# ultrasonic-breakout-pth.net
KiCad netlist of a schematic drawn in EAGLE
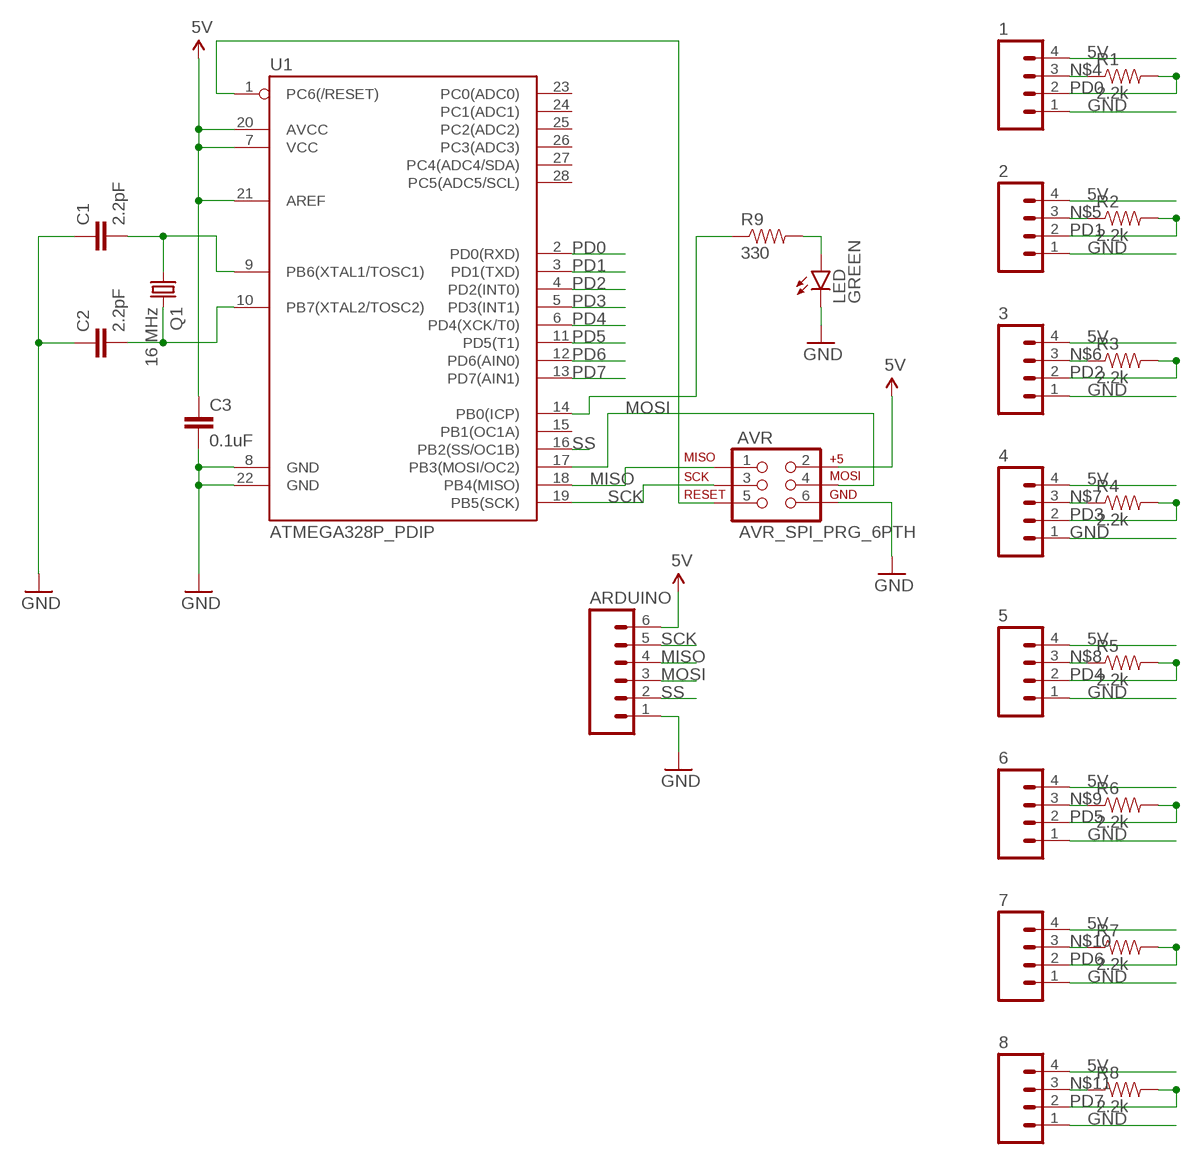
[diagram p0: schematic, sheet 1]

(export (version "E")
  (design (tool "Eeschema 10.0.6"))
  (components
    (comp (ref "1")
      (value "M04LOCK")
      (footprint "eagle-import:1X04_LOCK")
      (libsource (lib "eagle-import") (part "M04LOCK"))
    )
    (comp (ref "2")
      (value "M04LOCK")
      (footprint "eagle-import:1X04_LOCK")
      (libsource (lib "eagle-import") (part "M04LOCK"))
    )
    (comp (ref "3")
      (value "M04LOCK")
      (footprint "eagle-import:1X04_LOCK")
      (libsource (lib "eagle-import") (part "M04LOCK"))
    )
    (comp (ref "4")
      (value "M04LOCK")
      (footprint "eagle-import:1X04_LOCK")
      (libsource (lib "eagle-import") (part "M04LOCK"))
    )
    (comp (ref "5")
      (value "M04LOCK")
      (footprint "eagle-import:1X04_LOCK")
      (libsource (lib "eagle-import") (part "M04LOCK"))
    )
    (comp (ref "6")
      (value "M04LOCK")
      (footprint "eagle-import:1X04_LOCK")
      (libsource (lib "eagle-import") (part "M04LOCK"))
    )
    (comp (ref "7")
      (value "M04LOCK")
      (footprint "eagle-import:1X04_LOCK")
      (libsource (lib "eagle-import") (part "M04LOCK"))
    )
    (comp (ref "8")
      (value "M04LOCK")
      (footprint "eagle-import:1X04_LOCK")
      (libsource (lib "eagle-import") (part "M04LOCK"))
    )
    (comp (ref "ARDUINO")
      (value "M06LOCK")
      (footprint "eagle-import:1X06_LOCK")
      (libsource (lib "eagle-import") (part "M06LOCK"))
    )
    (comp (ref "AVR")
      (value "AVR_SPI_PRG_6PTH")
      (footprint "eagle-import:2X3")
      (libsource (lib "eagle-import") (part "AVR_SPI_PRG_6PTH"))
    )
    (comp (ref "C1")
      (value "2.2pF")
      (footprint "eagle-import:CAP-PTH-SMALL")
      (libsource (lib "eagle-import") (part "SparkFun-Passives_CAPPTH"))
    )
    (comp (ref "C2")
      (value "2.2pF")
      (footprint "eagle-import:CAP-PTH-SMALL")
      (libsource (lib "eagle-import") (part "SparkFun-Passives_CAPPTH"))
    )
    (comp (ref "C3")
      (value "0.1uF")
      (footprint "eagle-import:CAP-PTH-5MM")
      (libsource (lib "eagle-import") (part "CAPPTH1"))
    )
    (comp (ref "LED")
      (value "GREEN")
      (footprint "eagle-import:LED5MM")
      (libsource (lib "eagle-import") (part "LED5MM"))
    )
    (comp (ref "Q1")
      (value "16 MHz")
      (footprint "eagle-import:HC49U-V")
      (libsource (lib "eagle-import") (part "CRYSTALHC49UV"))
    )
    (comp (ref "R1")
      (value "2.2k")
      (footprint "eagle-import:AXIAL-0.4")
      (libsource (lib "eagle-import") (part "RESISTORPTH-1/4W"))
    )
    (comp (ref "R2")
      (value "2.2k")
      (footprint "eagle-import:AXIAL-0.4")
      (libsource (lib "eagle-import") (part "RESISTORPTH-1/4W"))
    )
    (comp (ref "R3")
      (value "2.2k")
      (footprint "eagle-import:AXIAL-0.4")
      (libsource (lib "eagle-import") (part "RESISTORPTH-1/4W"))
    )
    (comp (ref "R4")
      (value "2.2k")
      (footprint "eagle-import:AXIAL-0.4")
      (libsource (lib "eagle-import") (part "RESISTORPTH-1/4W"))
    )
    (comp (ref "R5")
      (value "2.2k")
      (footprint "eagle-import:AXIAL-0.4")
      (libsource (lib "eagle-import") (part "RESISTORPTH-1/4W"))
    )
    (comp (ref "R6")
      (value "2.2k")
      (footprint "eagle-import:AXIAL-0.4")
      (libsource (lib "eagle-import") (part "RESISTORPTH-1/4W"))
    )
    (comp (ref "R7")
      (value "2.2k")
      (footprint "eagle-import:AXIAL-0.4")
      (libsource (lib "eagle-import") (part "RESISTORPTH-1/4W"))
    )
    (comp (ref "R8")
      (value "2.2k")
      (footprint "eagle-import:AXIAL-0.4")
      (libsource (lib "eagle-import") (part "RESISTORPTH-1/4W"))
    )
    (comp (ref "R9")
      (value "330")
      (footprint "eagle-import:AXIAL-0.4")
      (libsource (lib "eagle-import") (part "RESISTORPTH-1/4W"))
    )
    (comp (ref "U1")
      (value "ATMEGA328P_PDIP")
      (footprint "eagle-import:DIL28-3")
      (libsource (lib "eagle-import") (part "ATMEGA328P_PDIP"))
    )
  )
  (nets
    (net (code "1") (name "/MISO") (class "Default")
      (node (ref "ARDUINO") (pin "4") (pinfunction "4_4") (pintype "passive"))
      (node (ref "AVR") (pin "1") (pinfunction "1_1") (pintype "passive"))
      (node (ref "U1") (pin "18") (pinfunction "PB4(MISO)_18") (pintype "bidirectional"))
    )
    (net (code "2") (name "/MOSI") (class "Default")
      (node (ref "ARDUINO") (pin "3") (pinfunction "3_3") (pintype "passive"))
      (node (ref "AVR") (pin "4") (pinfunction "4_4") (pintype "passive"))
      (node (ref "U1") (pin "17") (pinfunction "PB3(MOSI/OC2)_17") (pintype "bidirectional"))
    )
    (net (code "3") (name "/N$4") (class "Default")
      (node (ref "1") (pin "3") (pinfunction "3_3") (pintype "passive"))
      (node (ref "R1") (pin "P$1") (pinfunction "1_P$1") (pintype "passive"))
    )
    (net (code "4") (name "/N$5") (class "Default")
      (node (ref "2") (pin "3") (pinfunction "3_3") (pintype "passive"))
      (node (ref "R2") (pin "P$1") (pinfunction "1_P$1") (pintype "passive"))
    )
    (net (code "5") (name "/N$6") (class "Default")
      (node (ref "3") (pin "3") (pinfunction "3_3") (pintype "passive"))
      (node (ref "R3") (pin "P$1") (pinfunction "1_P$1") (pintype "passive"))
    )
    (net (code "6") (name "/N$7") (class "Default")
      (node (ref "4") (pin "3") (pinfunction "3_3") (pintype "passive"))
      (node (ref "R4") (pin "P$1") (pinfunction "1_P$1") (pintype "passive"))
    )
    (net (code "7") (name "/N$8") (class "Default")
      (node (ref "5") (pin "3") (pinfunction "3_3") (pintype "passive"))
      (node (ref "R5") (pin "P$1") (pinfunction "1_P$1") (pintype "passive"))
    )
    (net (code "8") (name "/N$9") (class "Default")
      (node (ref "6") (pin "3") (pinfunction "3_3") (pintype "passive"))
      (node (ref "R6") (pin "P$1") (pinfunction "1_P$1") (pintype "passive"))
    )
    (net (code "9") (name "/N$10") (class "Default")
      (node (ref "7") (pin "3") (pinfunction "3_3") (pintype "passive"))
      (node (ref "R7") (pin "P$1") (pinfunction "1_P$1") (pintype "passive"))
    )
    (net (code "10") (name "/N$11") (class "Default")
      (node (ref "8") (pin "3") (pinfunction "3_3") (pintype "passive"))
      (node (ref "R8") (pin "P$1") (pinfunction "1_P$1") (pintype "passive"))
    )
    (net (code "11") (name "/PD0") (class "Default")
      (node (ref "1") (pin "2") (pinfunction "2_2") (pintype "passive"))
      (node (ref "R1") (pin "P$2") (pinfunction "2_P$2") (pintype "passive"))
      (node (ref "U1") (pin "2") (pinfunction "PD0(RXD)_2") (pintype "bidirectional"))
    )
    (net (code "12") (name "/PD1") (class "Default")
      (node (ref "2") (pin "2") (pinfunction "2_2") (pintype "passive"))
      (node (ref "R2") (pin "P$2") (pinfunction "2_P$2") (pintype "passive"))
      (node (ref "U1") (pin "3") (pinfunction "PD1(TXD)_3") (pintype "bidirectional"))
    )
    (net (code "13") (name "/PD2") (class "Default")
      (node (ref "3") (pin "2") (pinfunction "2_2") (pintype "passive"))
      (node (ref "R3") (pin "P$2") (pinfunction "2_P$2") (pintype "passive"))
      (node (ref "U1") (pin "4") (pinfunction "PD2(INT0)_4") (pintype "bidirectional"))
    )
    (net (code "14") (name "/PD3") (class "Default")
      (node (ref "4") (pin "2") (pinfunction "2_2") (pintype "passive"))
      (node (ref "R4") (pin "P$2") (pinfunction "2_P$2") (pintype "passive"))
      (node (ref "U1") (pin "5") (pinfunction "PD3(INT1)_5") (pintype "bidirectional"))
    )
    (net (code "15") (name "/PD4") (class "Default")
      (node (ref "5") (pin "2") (pinfunction "2_2") (pintype "passive"))
      (node (ref "R5") (pin "P$2") (pinfunction "2_P$2") (pintype "passive"))
      (node (ref "U1") (pin "6") (pinfunction "PD4(XCK/T0)_6") (pintype "bidirectional"))
    )
    (net (code "16") (name "/PD5") (class "Default")
      (node (ref "6") (pin "2") (pinfunction "2_2") (pintype "passive"))
      (node (ref "R6") (pin "P$2") (pinfunction "2_P$2") (pintype "passive"))
      (node (ref "U1") (pin "11") (pinfunction "PD5(T1)_11") (pintype "bidirectional"))
    )
    (net (code "17") (name "/PD6") (class "Default")
      (node (ref "7") (pin "2") (pinfunction "2_2") (pintype "passive"))
      (node (ref "R7") (pin "P$2") (pinfunction "2_P$2") (pintype "passive"))
      (node (ref "U1") (pin "12") (pinfunction "PD6(AIN0)_12") (pintype "bidirectional"))
    )
    (net (code "18") (name "/PD7") (class "Default")
      (node (ref "8") (pin "2") (pinfunction "2_2") (pintype "passive"))
      (node (ref "R8") (pin "P$2") (pinfunction "2_P$2") (pintype "passive"))
      (node (ref "U1") (pin "13") (pinfunction "PD7(AIN1)_13") (pintype "bidirectional"))
    )
    (net (code "19") (name "/SCK") (class "Default")
      (node (ref "ARDUINO") (pin "5") (pinfunction "5_5") (pintype "passive"))
      (node (ref "AVR") (pin "3") (pinfunction "3_3") (pintype "passive"))
      (node (ref "U1") (pin "19") (pinfunction "PB5(SCK)_19") (pintype "bidirectional"))
    )
    (net (code "20") (name "/SS") (class "Default")
      (node (ref "ARDUINO") (pin "2") (pinfunction "2_2") (pintype "passive"))
      (node (ref "U1") (pin "16") (pinfunction "PB2(SS/OC1B)_16") (pintype "bidirectional"))
    )
    (net (code "21") (name "5V") (class "Default")
      (node (ref "1") (pin "4") (pinfunction "4_4") (pintype "passive"))
      (node (ref "2") (pin "4") (pinfunction "4_4") (pintype "passive"))
      (node (ref "3") (pin "4") (pinfunction "4_4") (pintype "passive"))
      (node (ref "4") (pin "4") (pinfunction "4_4") (pintype "passive"))
      (node (ref "5") (pin "4") (pinfunction "4_4") (pintype "passive"))
      (node (ref "6") (pin "4") (pinfunction "4_4") (pintype "passive"))
      (node (ref "7") (pin "4") (pinfunction "4_4") (pintype "passive"))
      (node (ref "8") (pin "4") (pinfunction "4_4") (pintype "passive"))
      (node (ref "ARDUINO") (pin "6") (pinfunction "6_6") (pintype "passive"))
      (node (ref "AVR") (pin "2") (pinfunction "2_2") (pintype "passive"))
      (node (ref "C3") (pin "1") (pinfunction "1_1") (pintype "passive"))
      (node (ref "U1") (pin "20") (pinfunction "AVCC_20") (pintype "bidirectional"))
      (node (ref "U1") (pin "21") (pinfunction "AREF_21") (pintype "bidirectional"))
      (node (ref "U1") (pin "7") (pinfunction "VCC_7") (pintype "bidirectional"))
    )
    (net (code "22") (name "GND") (class "Default")
      (node (ref "1") (pin "1") (pinfunction "1_1") (pintype "passive"))
      (node (ref "2") (pin "1") (pinfunction "1_1") (pintype "passive"))
      (node (ref "3") (pin "1") (pinfunction "1_1") (pintype "passive"))
      (node (ref "4") (pin "1") (pinfunction "1_1") (pintype "passive"))
      (node (ref "5") (pin "1") (pinfunction "1_1") (pintype "passive"))
      (node (ref "6") (pin "1") (pinfunction "1_1") (pintype "passive"))
      (node (ref "7") (pin "1") (pinfunction "1_1") (pintype "passive"))
      (node (ref "8") (pin "1") (pinfunction "1_1") (pintype "passive"))
      (node (ref "ARDUINO") (pin "1") (pinfunction "1_1") (pintype "passive"))
      (node (ref "AVR") (pin "6") (pinfunction "6_6") (pintype "passive"))
      (node (ref "C1") (pin "1") (pinfunction "1_1") (pintype "passive"))
      (node (ref "C2") (pin "1") (pinfunction "1_1") (pintype "passive"))
      (node (ref "C3") (pin "2") (pinfunction "2_2") (pintype "passive"))
      (node (ref "LED") (pin "K") (pinfunction "C_K") (pintype "passive"))
      (node (ref "U1") (pin "22") (pinfunction "GND_22") (pintype "bidirectional"))
      (node (ref "U1") (pin "8") (pinfunction "GND_8") (pintype "bidirectional"))
    )
    (net (code "23") (name "Net-(R9-1)") (class "Default")
      (node (ref "R9") (pin "P$1") (pinfunction "1_P$1") (pintype "passive"))
      (node (ref "U1") (pin "14") (pinfunction "PB0(ICP)_14") (pintype "bidirectional"))
    )
    (net (code "24") (name "Net-(R9-2)") (class "Default")
      (node (ref "LED") (pin "A") (pinfunction "A_A") (pintype "passive"))
      (node (ref "R9") (pin "P$2") (pinfunction "2_P$2") (pintype "passive"))
    )
    (net (code "25") (name "Net-(U1-PB6(XTAL1{slash}TOSC1))") (class "Default")
      (node (ref "C1") (pin "2") (pinfunction "2_2") (pintype "passive"))
      (node (ref "Q1") (pin "1") (pinfunction "1_1") (pintype "passive"))
      (node (ref "U1") (pin "9") (pinfunction "PB6(XTAL1/TOSC1)_9") (pintype "bidirectional"))
    )
    (net (code "26") (name "Net-(U1-PB7(XTAL2{slash}TOSC2))") (class "Default")
      (node (ref "C2") (pin "2") (pinfunction "2_2") (pintype "passive"))
      (node (ref "Q1") (pin "2") (pinfunction "2_2") (pintype "passive"))
      (node (ref "U1") (pin "10") (pinfunction "PB7(XTAL2/TOSC2)_10") (pintype "bidirectional"))
    )
    (net (code "27") (name "Net-(U1-PC6({slash}RESET))") (class "Default")
      (node (ref "AVR") (pin "5") (pinfunction "5_5") (pintype "passive"))
      (node (ref "U1") (pin "1") (pinfunction "PC6(/RESET)_1") (pintype "bidirectional"))
    )
    (net (code "28") (name "unconnected-(U1-PB1(OC1A)-Pad15)") (class "Default")
      (node (ref "U1") (pin "15") (pinfunction "PB1(OC1A)_15") (pintype "bidirectional"))
    )
    (net (code "29") (name "unconnected-(U1-PC0(ADC0)-Pad23)") (class "Default")
      (node (ref "U1") (pin "23") (pinfunction "PC0(ADC0)_23") (pintype "bidirectional"))
    )
    (net (code "30") (name "unconnected-(U1-PC1(ADC1)-Pad24)") (class "Default")
      (node (ref "U1") (pin "24") (pinfunction "PC1(ADC1)_24") (pintype "bidirectional"))
    )
    (net (code "31") (name "unconnected-(U1-PC2(ADC2)-Pad25)") (class "Default")
      (node (ref "U1") (pin "25") (pinfunction "PC2(ADC2)_25") (pintype "bidirectional"))
    )
    (net (code "32") (name "unconnected-(U1-PC3(ADC3)-Pad26)") (class "Default")
      (node (ref "U1") (pin "26") (pinfunction "PC3(ADC3)_26") (pintype "bidirectional"))
    )
    (net (code "33") (name "unconnected-(U1-PC4(ADC4{slash}SDA)-Pad27)") (class "Default")
      (node (ref "U1") (pin "27") (pinfunction "PC4(ADC4/SDA)_27") (pintype "bidirectional"))
    )
    (net (code "34") (name "unconnected-(U1-PC5(ADC5{slash}SCL)-Pad28)") (class "Default")
      (node (ref "U1") (pin "28") (pinfunction "PC5(ADC5/SCL)_28") (pintype "bidirectional"))
    )
  )
)
